# 20190105_ORIGAMI_V1-H-P.net
KiCad netlist of a schematic drawn in EAGLE
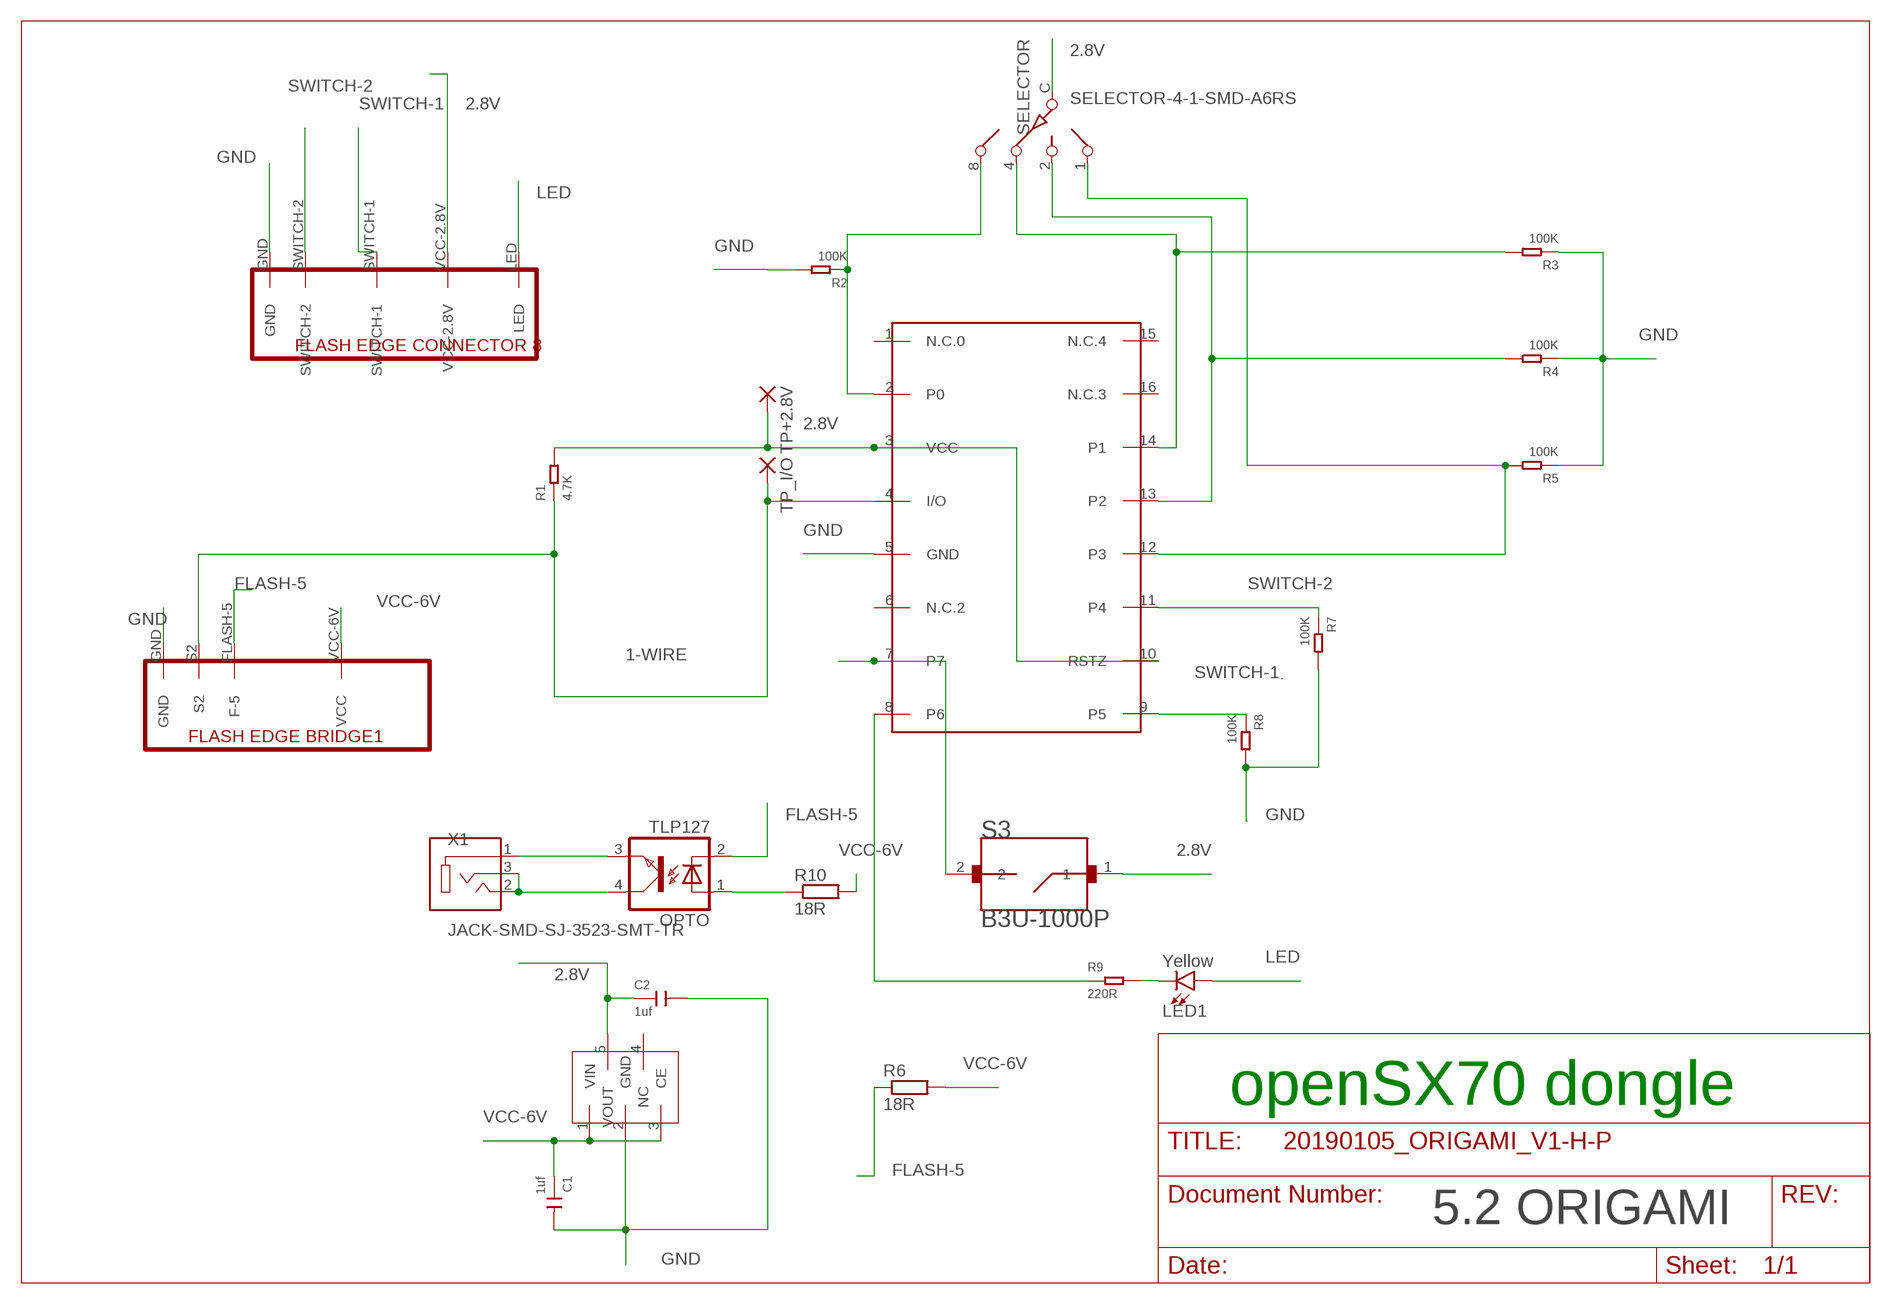
[diagram p0: schematic, sheet 1]

(export (version "E")
  (design (tool "Eeschema 10.0.6"))
  (components
    (comp (ref "C1")
      (value "1uf")
      (footprint "eagle-import:C0603")
      (fields (field (name "MPN") "CC0603KRX7R8BB105"))
      (libsource (lib "eagle-import") (part "CERAMIC-1UF-25V-10%-X7R(0603)"))
    )
    (comp (ref "C2")
      (value "1uf")
      (footprint "eagle-import:C0603")
      (fields (field (name "MPN") "CC0603KRX7R8BB105"))
      (libsource (lib "eagle-import") (part "CERAMIC-1UF-25V-10%-X7R(0603)"))
    )
    (comp (ref "DS2408")
      (value "DS2408")
      (footprint "eagle-import:SO16")
      (libsource (lib "eagle-import") (part "DS2408"))
    )
    (comp (ref "LED1")
      (value "Yellow")
      (footprint "eagle-import:LED-1206")
      (libsource (lib "eagle-import") (part "LED-YELLOWLILYPAD"))
    )
    (comp (ref "OPTO")
      (value "TLP127")
      (footprint "eagle-import:SO-4")
      (libsource (lib "eagle-import") (part "TLP127"))
    )
    (comp (ref "R1")
      (value "4.7K")
      (footprint "eagle-import:R0603")
      (fields (field (name "MPN") "RC0603JR-074K7L"))
      (libsource (lib "eagle-import") (part "SMD-RES-4.7K-5%-1/10W(0603)"))
    )
    (comp (ref "R2")
      (value "100K")
      (footprint "eagle-import:R0603")
      (fields (field (name "MPN") "RC0603FR-07100KL"))
      (libsource (lib "eagle-import") (part "SMD-RES-100K-1%-1/10W(0603)"))
    )
    (comp (ref "R3")
      (value "100K")
      (footprint "eagle-import:R0603")
      (fields (field (name "MPN") "RC0603FR-07100KL"))
      (libsource (lib "eagle-import") (part "SMD-RES-100K-1%-1/10W(0603)"))
    )
    (comp (ref "R4")
      (value "100K")
      (footprint "eagle-import:R0603")
      (fields (field (name "MPN") "RC0603FR-07100KL"))
      (libsource (lib "eagle-import") (part "SMD-RES-100K-1%-1/10W(0603)"))
    )
    (comp (ref "R5")
      (value "100K")
      (footprint "eagle-import:R0603")
      (fields (field (name "MPN") "RC0603FR-07100KL"))
      (libsource (lib "eagle-import") (part "SMD-RES-100K-1%-1/10W(0603)"))
    )
    (comp (ref "R6")
      (value "18R")
      (footprint "eagle-import:R0603")
      (libsource (lib "eagle-import") (part "R-EU_R0603"))
    )
    (comp (ref "R7")
      (value "100K")
      (footprint "eagle-import:R0603")
      (fields (field (name "MPN") "RC0603FR-07100KL"))
      (libsource (lib "eagle-import") (part "SMD-RES-100K-1%-1/10W(0603)"))
    )
    (comp (ref "R8")
      (value "100K")
      (footprint "eagle-import:R0603")
      (fields (field (name "MPN") "RC0603FR-07100KL"))
      (libsource (lib "eagle-import") (part "SMD-RES-100K-1%-1/10W(0603)"))
    )
    (comp (ref "R9")
      (value "220R")
      (footprint "eagle-import:R0603")
      (fields (field (name "MPN") "RC0603JR-07220RL"))
      (libsource (lib "eagle-import") (part "SMD-RES-220R-5%-1/10W(0603)"))
    )
    (comp (ref "R10")
      (value "18R")
      (footprint "eagle-import:R0603")
      (libsource (lib "eagle-import") (part "R-EU_R0603"))
    )
    (comp (ref "REG")
      (value "NCP4688")
      (footprint "eagle-import:SOT-23-5")
      (libsource (lib "eagle-import") (part "NCP4688"))
    )
    (comp (ref "S3")
      (value "B3U-1000P")
      (footprint "eagle-import:SW_B3U-1000P")
      (fields (field (name "MANUFACTURER") "Omron"))
      (libsource (lib "eagle-import") (part "B3U-1000P"))
    )
    (comp (ref "SELECTOR")
      (value "SELECTOR-4-1-SMD-A6RS")
      (footprint "eagle-import:A6RS-161RS")
      (libsource (lib "eagle-import") (part "SELECTOR-4-1-SMD-A6RS"))
    )
    (comp (ref "TP+2.8V")
      (value "SMD2")
      (footprint "eagle-import:SMD1,27-2,54")
      (libsource (lib "eagle-import") (part "SMD2"))
    )
    (comp (ref "TP_I/O")
      (value "SMD2")
      (footprint "eagle-import:SMD1,27-2,54")
      (libsource (lib "eagle-import") (part "SMD2"))
    )
    (comp (ref "U$1")
      (value "FLASH-BRIDGE-SW1-SW2-LED")
      (footprint "eagle-import:FLASH-8-BRIDGE-SW1-SW2-LED")
      (libsource (lib "eagle-import") (part "FLASH-BRIDGE-SW1-SW2-LED"))
    )
    (comp (ref "U$2")
      (value "FLASH-BRIDGE1")
      (footprint "eagle-import:FLASH-8-BRIDGE1")
      (libsource (lib "eagle-import") (part "FLASH-BRIDGE1"))
    )
    (comp (ref "X1")
      (value "JACK-SMD-SJ-3523-SMT-TR")
      (footprint "eagle-import:CUI_SJ-3523-SMT-TR")
      (fields (field (name "MF") "CUI Inc.") (field (name "MP") "SJ-3523-SMT-TR"))
      (libsource (lib "eagle-import") (part "JACK-SMD-SJ-3523-SMT-TR"))
    )
  )
  (nets
    (net (code "1") (name "/1-WIRE") (class "Default")
      (node (ref "DS2408") (pin "4") (pinfunction "I/O_4") (pintype "bidirectional"))
      (node (ref "R1") (pin "1") (pinfunction "1_1") (pintype "passive"))
      (node (ref "TP_I/O") (pin "1") (pinfunction "P_1") (pintype "passive"))
      (node (ref "U$2") (pin "S2") (pinfunction "S2_S2") (pintype "bidirectional"))
    )
    (net (code "2") (name "/2.8V") (class "Default")
      (node (ref "C2") (pin "1") (pinfunction "1_1") (pintype "passive"))
      (node (ref "DS2408") (pin "10") (pinfunction "RSTZ_10") (pintype "bidirectional"))
      (node (ref "DS2408") (pin "3") (pinfunction "VCC_3") (pintype "bidirectional"))
      (node (ref "R1") (pin "2") (pinfunction "2_2") (pintype "passive"))
      (node (ref "REG") (pin "5") (pinfunction "VOUT_5") (pintype "bidirectional"))
      (node (ref "S3") (pin "1") (pinfunction "1_1") (pintype "passive"))
      (node (ref "SELECTOR") (pin "C") (pinfunction "C_C") (pintype "passive"))
      (node (ref "TP+2.8V") (pin "1") (pinfunction "P_1") (pintype "passive"))
      (node (ref "U$1") (pin "VCC-2.8V") (pinfunction "VCC-2.8V_VCC-2.8V") (pintype "bidirectional"))
    )
    (net (code "3") (name "/FLASH-5") (class "Default")
      (node (ref "OPTO") (pin "2") (pinfunction "C_2") (pintype "passive"))
      (node (ref "R6") (pin "1") (pinfunction "1_1") (pintype "passive"))
      (node (ref "U$2") (pin "FLASH-5") (pinfunction "F-5_FLASH-5") (pintype "bidirectional"))
    )
    (net (code "4") (name "/GND") (class "Default")
      (node (ref "C1") (pin "2") (pinfunction "2_2") (pintype "passive"))
      (node (ref "C2") (pin "2") (pinfunction "2_2") (pintype "passive"))
      (node (ref "DS2408") (pin "5") (pinfunction "GND_5") (pintype "bidirectional"))
      (node (ref "R2") (pin "2") (pinfunction "2_2") (pintype "passive"))
      (node (ref "R3") (pin "1") (pinfunction "1_1") (pintype "passive"))
      (node (ref "R4") (pin "1") (pinfunction "1_1") (pintype "passive"))
      (node (ref "R5") (pin "1") (pinfunction "1_1") (pintype "passive"))
      (node (ref "R7") (pin "2") (pinfunction "2_2") (pintype "passive"))
      (node (ref "R8") (pin "2") (pinfunction "2_2") (pintype "passive"))
      (node (ref "REG") (pin "2") (pinfunction "GND_2") (pintype "bidirectional"))
      (node (ref "U$1") (pin "GND") (pinfunction "GND_GND") (pintype "bidirectional"))
      (node (ref "U$2") (pin "GND") (pinfunction "GND_GND") (pintype "bidirectional"))
    )
    (net (code "5") (name "/LED") (class "Default")
      (node (ref "LED1") (pin "A") (pinfunction "A_A") (pintype "passive"))
      (node (ref "U$1") (pin "LED") (pinfunction "LED_LED") (pintype "bidirectional"))
    )
    (net (code "6") (name "/SWITCH-1") (class "Default")
      (node (ref "DS2408") (pin "9") (pinfunction "P5_9") (pintype "bidirectional"))
      (node (ref "R8") (pin "1") (pinfunction "1_1") (pintype "passive"))
      (node (ref "U$1") (pin "SWITCH-1") (pinfunction "SWITCH-1_SWITCH-1") (pintype "bidirectional"))
    )
    (net (code "7") (name "/SWITCH-2") (class "Default")
      (node (ref "DS2408") (pin "11") (pinfunction "P4_11") (pintype "bidirectional"))
      (node (ref "R7") (pin "1") (pinfunction "1_1") (pintype "passive"))
      (node (ref "U$1") (pin "SWITCH-2") (pinfunction "SWITCH-2_SWITCH-2") (pintype "bidirectional"))
    )
    (net (code "8") (name "/VCC-6V") (class "Default")
      (node (ref "C1") (pin "1") (pinfunction "1_1") (pintype "passive"))
      (node (ref "R10") (pin "2") (pinfunction "2_2") (pintype "passive"))
      (node (ref "R6") (pin "2") (pinfunction "2_2") (pintype "passive"))
      (node (ref "REG") (pin "1") (pinfunction "VIN_1") (pintype "bidirectional"))
      (node (ref "REG") (pin "3") (pinfunction "CE_3") (pintype "bidirectional"))
      (node (ref "U$2") (pin "VCC-6V") (pinfunction "VCC_VCC-6V") (pintype "bidirectional"))
    )
    (net (code "9") (name "Net-(DS2408-P0)") (class "Default")
      (node (ref "DS2408") (pin "2") (pinfunction "P0_2") (pintype "bidirectional"))
      (node (ref "R2") (pin "1") (pinfunction "1_1") (pintype "passive"))
      (node (ref "SELECTOR") (pin "8") (pinfunction "8_8") (pintype "passive"))
    )
    (net (code "10") (name "Net-(DS2408-P1)") (class "Default")
      (node (ref "DS2408") (pin "14") (pinfunction "P1_14") (pintype "bidirectional"))
      (node (ref "R3") (pin "2") (pinfunction "2_2") (pintype "passive"))
      (node (ref "SELECTOR") (pin "4") (pinfunction "4_4") (pintype "passive"))
    )
    (net (code "11") (name "Net-(DS2408-P2)") (class "Default")
      (node (ref "DS2408") (pin "13") (pinfunction "P2_13") (pintype "bidirectional"))
      (node (ref "R4") (pin "2") (pinfunction "2_2") (pintype "passive"))
      (node (ref "SELECTOR") (pin "2") (pinfunction "2_2") (pintype "passive"))
    )
    (net (code "12") (name "Net-(DS2408-P3)") (class "Default")
      (node (ref "DS2408") (pin "12") (pinfunction "P3_12") (pintype "bidirectional"))
      (node (ref "R5") (pin "2") (pinfunction "2_2") (pintype "passive"))
      (node (ref "SELECTOR") (pin "1") (pinfunction "1_1") (pintype "passive"))
    )
    (net (code "13") (name "Net-(DS2408-P6)") (class "Default")
      (node (ref "DS2408") (pin "8") (pinfunction "P6_8") (pintype "bidirectional"))
      (node (ref "R9") (pin "1") (pinfunction "1_1") (pintype "passive"))
    )
    (net (code "14") (name "Net-(DS2408-P7)") (class "Default")
      (node (ref "DS2408") (pin "7") (pinfunction "P7_7") (pintype "bidirectional"))
      (node (ref "S3") (pin "2") (pinfunction "2_2") (pintype "passive"))
    )
    (net (code "15") (name "Net-(LED1-PadC)") (class "Default")
      (node (ref "LED1") (pin "C") (pinfunction "C_C") (pintype "passive"))
      (node (ref "R9") (pin "2") (pinfunction "2_2") (pintype "passive"))
    )
    (net (code "16") (name "Net-(OPTO-A)") (class "Default")
      (node (ref "OPTO") (pin "1") (pinfunction "A_1") (pintype "passive"))
      (node (ref "R10") (pin "1") (pinfunction "1_1") (pintype "passive"))
    )
    (net (code "17") (name "Net-(OPTO-COL)") (class "Default")
      (node (ref "OPTO") (pin "4") (pinfunction "COL_4") (pintype "passive"))
      (node (ref "X1") (pin "2") (pinfunction "2_2") (pintype "passive"))
      (node (ref "X1") (pin "3") (pinfunction "3_3") (pintype "passive"))
    )
    (net (code "18") (name "Net-(OPTO-EMIT)") (class "Default")
      (node (ref "OPTO") (pin "3") (pinfunction "EMIT_3") (pintype "passive"))
      (node (ref "X1") (pin "1") (pinfunction "1_1") (pintype "passive"))
    )
    (net (code "19") (name "unconnected-(DS2408-N.C.0-Pad1)") (class "Default")
      (node (ref "DS2408") (pin "1") (pinfunction "N.C.0_1") (pintype "bidirectional"))
    )
    (net (code "20") (name "unconnected-(DS2408-N.C.2-Pad6)") (class "Default")
      (node (ref "DS2408") (pin "6") (pinfunction "N.C.2_6") (pintype "bidirectional"))
    )
    (net (code "21") (name "unconnected-(DS2408-N.C.3-Pad16)") (class "Default")
      (node (ref "DS2408") (pin "16") (pinfunction "N.C.3_16") (pintype "bidirectional"))
    )
    (net (code "22") (name "unconnected-(DS2408-N.C.4-Pad15)") (class "Default")
      (node (ref "DS2408") (pin "15") (pinfunction "N.C.4_15") (pintype "bidirectional"))
    )
    (net (code "23") (name "unconnected-(REG-NC-Pad4)") (class "Default")
      (node (ref "REG") (pin "4") (pinfunction "NC_4") (pintype "bidirectional"))
    )
  )
)
